# AudioSwitch.net
KiCad netlist of a schematic drawn in EAGLE
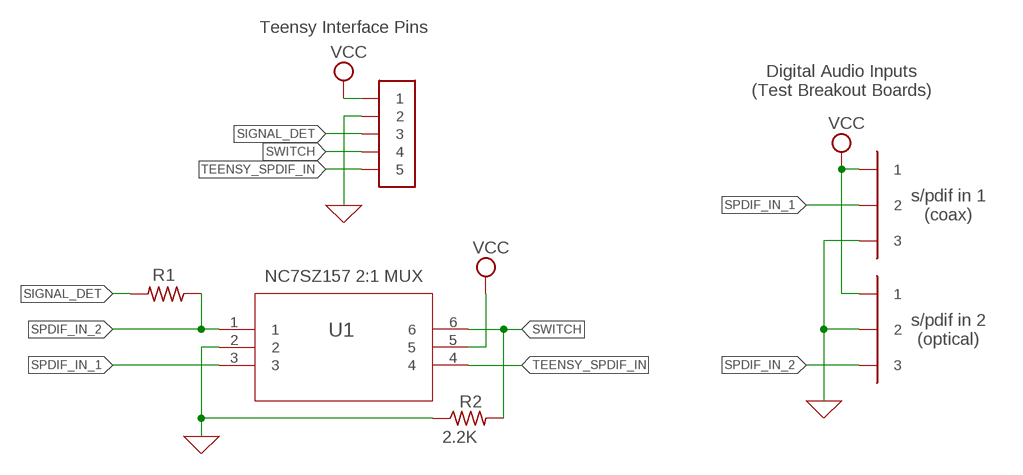
[diagram p0: schematic, sheet 1]

(export (version "E")
  (design (tool "Eeschema 10.0.6"))
  (components
    (comp (ref "R1")
      (value "R-US_R0603")
      (footprint "eagle-import:R0603")
      (libsource (lib "eagle-import") (part "R-US_R0603"))
    )
    (comp (ref "R2")
      (value "2.2K")
      (footprint "eagle-import:R0603")
      (libsource (lib "eagle-import") (part "R-US_R0603"))
    )
    (comp (ref "U$1")
      (value "1X5HEADER")
      (footprint "eagle-import:1X5HEADER")
      (libsource (lib "eagle-import") (part "1X5HEADER"))
    )
    (comp (ref "U$2")
      (value "1X3HEADER")
      (footprint "eagle-import:1X3HEADER")
      (libsource (lib "eagle-import") (part "1X3HEADER"))
    )
    (comp (ref "U$3")
      (value "1X3HEADER")
      (footprint "eagle-import:1X3HEADER")
      (libsource (lib "eagle-import") (part "1X3HEADER"))
    )
    (comp (ref "U1")
      (value "2:1_MUX_NC7SZ157P6X")
      (footprint "eagle-import:SOIC_Z157P6X_ONS")
      (fields (field (name "MANUFACTURER_PART_NUMBER") "NC7SZ157P6X"))
      (libsource (lib "eagle-import") (part "2{colon}1_MUX_NC7SZ157P6X"))
    )
  )
  (nets
    (net (code "1") (name "GND") (class "Default")
      (node (ref "R2") (pin "1") (pinfunction "1_1") (pintype "passive"))
      (node (ref "U$1") (pin "P$2") (pinfunction "2_P$2") (pintype "bidirectional"))
      (node (ref "U$2") (pin "P$3") (pinfunction "3_P$3") (pintype "bidirectional"))
      (node (ref "U$3") (pin "P$2") (pinfunction "2_P$2") (pintype "bidirectional"))
      (node (ref "U1") (pin "2") (pinfunction "2_2") (pintype "passive"))
    )
    (net (code "2") (name "SIGNAL_DET") (class "Default")
      (node (ref "R1") (pin "2") (pinfunction "2_2") (pintype "passive"))
      (node (ref "U$1") (pin "P$3") (pinfunction "3_P$3") (pintype "bidirectional"))
    )
    (net (code "3") (name "SPDIF_IN_1") (class "Default")
      (node (ref "U$2") (pin "P$2") (pinfunction "2_P$2") (pintype "bidirectional"))
      (node (ref "U1") (pin "3") (pinfunction "3_3") (pintype "bidirectional"))
    )
    (net (code "4") (name "SPDIF_IN_2") (class "Default")
      (node (ref "R1") (pin "1") (pinfunction "1_1") (pintype "passive"))
      (node (ref "U$3") (pin "P$3") (pinfunction "3_P$3") (pintype "bidirectional"))
      (node (ref "U1") (pin "1") (pinfunction "1_1") (pintype "bidirectional"))
    )
    (net (code "5") (name "SWITCH") (class "Default")
      (node (ref "R2") (pin "2") (pinfunction "2_2") (pintype "passive"))
      (node (ref "U$1") (pin "P$4") (pinfunction "4_P$4") (pintype "bidirectional"))
      (node (ref "U1") (pin "6") (pinfunction "6_6") (pintype "passive"))
    )
    (net (code "6") (name "TEENSY_SPDIF_IN") (class "Default")
      (node (ref "U$1") (pin "P$5") (pinfunction "5_P$5") (pintype "bidirectional"))
      (node (ref "U1") (pin "4") (pinfunction "4_4") (pintype "passive"))
    )
    (net (code "7") (name "VCC") (class "Default")
      (node (ref "U$1") (pin "P$1") (pinfunction "1_P$1") (pintype "bidirectional"))
      (node (ref "U$2") (pin "P$1") (pinfunction "1_P$1") (pintype "bidirectional"))
      (node (ref "U$3") (pin "P$1") (pinfunction "1_P$1") (pintype "bidirectional"))
      (node (ref "U1") (pin "5") (pinfunction "5_5") (pintype "power_in"))
    )
  )
)
